# usb2ttl.net
KiCad netlist of a schematic drawn in Altium Designer
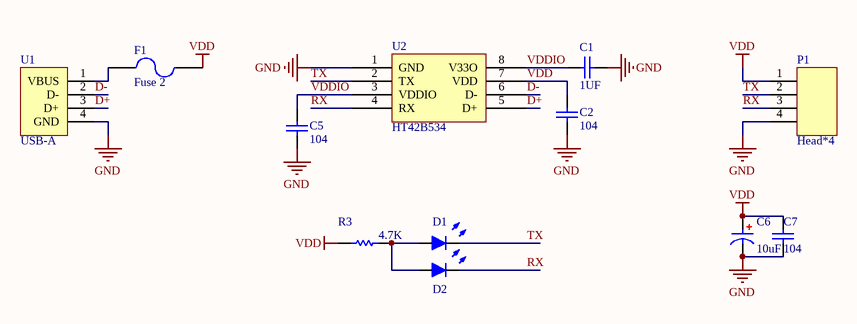
[diagram p0: usb2ttl.SchDoc]

(export (version "E")
  (design (tool "Eeschema 10.0.6"))
  (components
    (comp (ref "C1")
      (value "C1uF")
      (footprint "0603C")
      (fields (field (name "ALTIUM_UNNAMED_1") "1UF"))
      (libsource (lib "OKmeSchLibrary") (part "C0.1uF"))
    )
    (comp (ref "C2")
      (value "104")
      (footprint "0603C")
      (fields (field (name "ALTIUM_UNNAMED_1") "104"))
      (libsource (lib "OKmeSchLibrary") (part "C0.1uF"))
    )
    (comp (ref "C5")
      (value "104")
      (footprint "0603C")
      (fields (field (name "ALTIUM_UNNAMED_1") "104"))
      (libsource (lib "OKmeSchLibrary") (part "C0.1uF"))
    )
    (comp (ref "C6")
      (value "C10uF")
      (footprint "0603C")
      (fields (field (name "ALTIUM_UNNAMED_1") "10uF"))
      (libsource (lib "OKmeSchLibrary") (part "C10uF"))
    )
    (comp (ref "C7")
      (value "104")
      (footprint "0603C")
      (fields (field (name "ALTIUM_UNNAMED_1") "104"))
      (libsource (lib "OKmeSchLibrary") (part "C0.1uF"))
    )
    (comp (ref "D1") (value "LED-G") (footprint "LED") (libsource (lib "OKmeSchLibrary") (part "LED")))
    (comp (ref "D2") (value "LED-R") (footprint "LED") (libsource (lib "OKmeSchLibrary") (part "LED")))
    (comp (ref "F1")
      (value "Fuse 2")
      (footprint "0805")
      (description "Fuse")
      (fields (field (name "PUBLISHER") "Altium Limited"))
      (libsource (lib "Miscellaneous Devices") (part "Fuse 2"))
    )
    (comp (ref "P1") (value "Head*4") (footprint "HEAD*4") (libsource (lib "OKmeSchLibrary") (part "Head*4")))
    (comp (ref "R3")
      (value "R4.7K")
      (footprint "0603R")
      (fields (field (name "ALTIUM_UNNAMED_1") "4.7K"))
      (libsource (lib "OKmeSchLibrary") (part "R1K"))
    )
    (comp (ref "U1") (value "USB-A") (footprint "USB-A") (libsource (lib "OKmeSchLibrary") (part "USB-A")))
    (comp (ref "U2")
      (value "HT42B534")
      (footprint "SOP-8")
      (libsource (lib "OKmeSchLibrary") (part "HT42B534"))
    )
  )
  (nets
    (net (code "1") (name "/D+") (class "Default")
      (node (ref "U1") (pin "3") (pinfunction "D+_3") (pintype "passive"))
      (node (ref "U2") (pin "5") (pinfunction "D+_5") (pintype "passive"))
    )
    (net (code "2") (name "/D-") (class "Default")
      (node (ref "U1") (pin "2") (pinfunction "D-_2") (pintype "passive"))
      (node (ref "U2") (pin "6") (pinfunction "D-_6") (pintype "passive"))
    )
    (net (code "3") (name "/RX") (class "Default")
      (node (ref "D2") (pin "2") (pinfunction "K_2") (pintype "passive"))
      (node (ref "P1") (pin "3") (pinfunction "3_3") (pintype "passive"))
      (node (ref "U2") (pin "4") (pinfunction "RX_4") (pintype "passive"))
    )
    (net (code "4") (name "/TX") (class "Default")
      (node (ref "D1") (pin "2") (pinfunction "K_2") (pintype "passive"))
      (node (ref "P1") (pin "2") (pinfunction "2_2") (pintype "passive"))
      (node (ref "U2") (pin "2") (pinfunction "TX_2") (pintype "passive"))
    )
    (net (code "5") (name "/VDDIO") (class "Default")
      (node (ref "C1") (pin "2") (pinfunction "2_2") (pintype "passive"))
      (node (ref "C5") (pin "1") (pinfunction "1_1") (pintype "passive"))
      (node (ref "U2") (pin "3") (pinfunction "VDDIO_3") (pintype "passive"))
      (node (ref "U2") (pin "8") (pinfunction "V33O_8") (pintype "passive"))
    )
    (net (code "6") (name "GND") (class "Default")
      (node (ref "C1") (pin "1") (pinfunction "1_1") (pintype "passive"))
      (node (ref "C2") (pin "2") (pinfunction "2_2") (pintype "passive"))
      (node (ref "C5") (pin "2") (pinfunction "2_2") (pintype "passive"))
      (node (ref "C6") (pin "2") (pinfunction "2_2") (pintype "passive"))
      (node (ref "C7") (pin "1") (pinfunction "1_1") (pintype "passive"))
      (node (ref "P1") (pin "4") (pinfunction "4_4") (pintype "passive"))
      (node (ref "U1") (pin "4") (pinfunction "GND_4") (pintype "passive"))
      (node (ref "U2") (pin "1") (pinfunction "GND_1") (pintype "passive"))
    )
    (net (code "7") (name "Net-(D1-A)") (class "Default")
      (node (ref "D1") (pin "1") (pinfunction "A_1") (pintype "passive"))
      (node (ref "D2") (pin "1") (pinfunction "A_1") (pintype "passive"))
      (node (ref "R3") (pin "2") (pinfunction "2_2") (pintype "passive"))
    )
    (net (code "8") (name "Net-(U1-VBUS)") (class "Default")
      (node (ref "F1") (pin "1") (pinfunction "1_1") (pintype "passive"))
      (node (ref "U1") (pin "1") (pinfunction "VBUS_1") (pintype "passive"))
    )
    (net (code "9") (name "VDD") (class "Default")
      (node (ref "C2") (pin "1") (pinfunction "1_1") (pintype "passive"))
      (node (ref "C6") (pin "1") (pinfunction "1_1") (pintype "passive"))
      (node (ref "C7") (pin "2") (pinfunction "2_2") (pintype "passive"))
      (node (ref "F1") (pin "2") (pinfunction "2_2") (pintype "passive"))
      (node (ref "P1") (pin "1") (pinfunction "1_1") (pintype "passive"))
      (node (ref "R3") (pin "1") (pinfunction "1_1") (pintype "passive"))
      (node (ref "U2") (pin "7") (pinfunction "VDD_7") (pintype "passive"))
    )
  )
)
